# mini1284.net
KiCad netlist of a schematic drawn in EAGLE
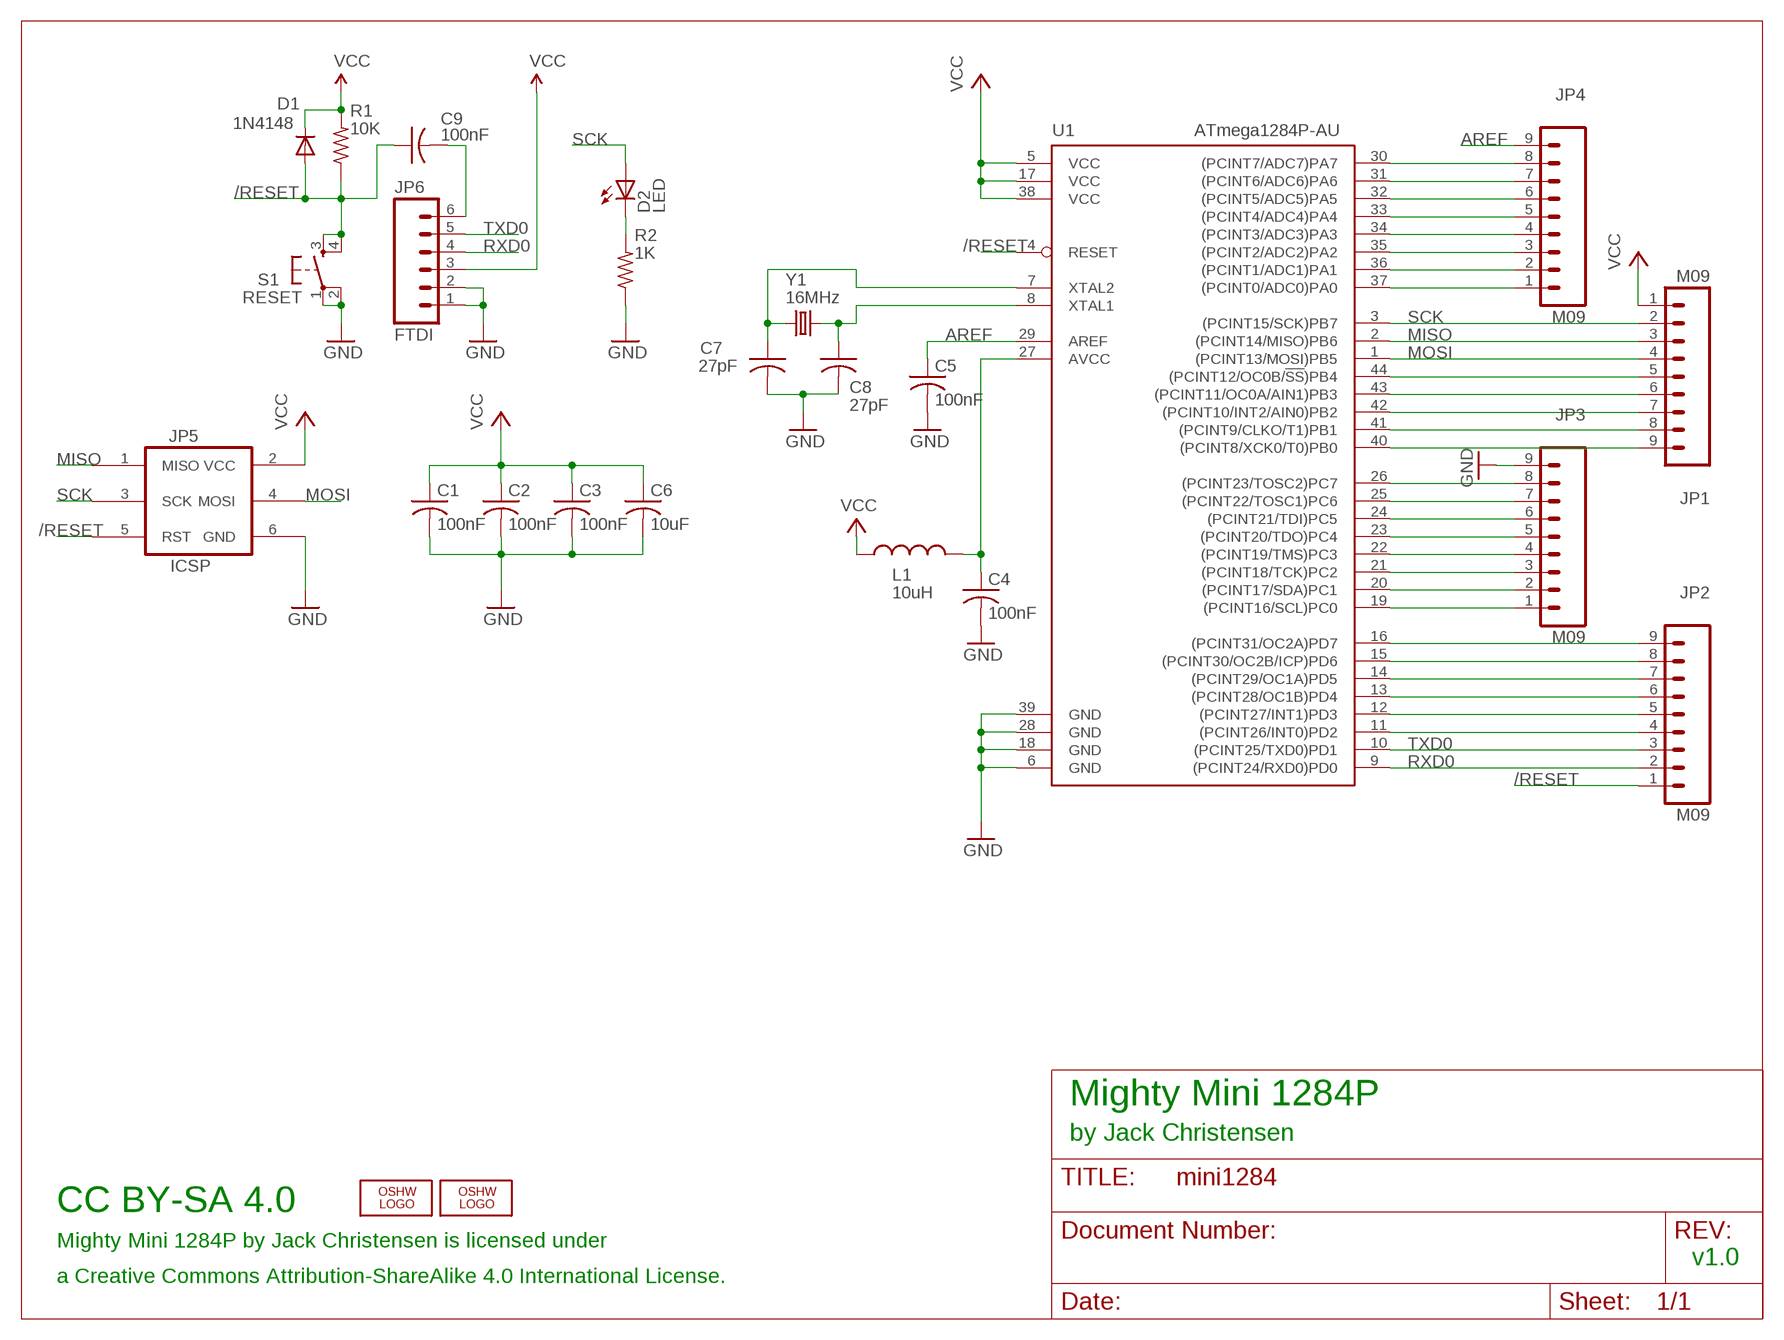
[diagram p0: schematic, sheet 1]

(export (version "E")
  (design (tool "Eeschema 10.0.6"))
  (components
    (comp (ref "C1")
      (value "100nF")
      (footprint "eagle-import:M0805")
      (libsource (lib "eagle-import") (part "C-USM0805"))
    )
    (comp (ref "C2")
      (value "100nF")
      (footprint "eagle-import:M0805")
      (libsource (lib "eagle-import") (part "C-USM0805"))
    )
    (comp (ref "C3")
      (value "100nF")
      (footprint "eagle-import:M0805")
      (libsource (lib "eagle-import") (part "C-USM0805"))
    )
    (comp (ref "C4")
      (value "100nF")
      (footprint "eagle-import:M0805")
      (libsource (lib "eagle-import") (part "C-USM0805"))
    )
    (comp (ref "C5")
      (value "100nF")
      (footprint "eagle-import:M0805")
      (libsource (lib "eagle-import") (part "C-USM0805"))
    )
    (comp (ref "C6")
      (value "10uF")
      (footprint "eagle-import:M1206")
      (libsource (lib "eagle-import") (part "C-USM1206"))
    )
    (comp (ref "C7")
      (value "27pF")
      (footprint "eagle-import:M0805")
      (libsource (lib "eagle-import") (part "C-USM0805"))
    )
    (comp (ref "C8")
      (value "27pF")
      (footprint "eagle-import:M0805")
      (libsource (lib "eagle-import") (part "C-USM0805"))
    )
    (comp (ref "C9")
      (value "100nF")
      (footprint "eagle-import:M0805")
      (libsource (lib "eagle-import") (part "C-USM0805"))
    )
    (comp (ref "D1")
      (value "1N4148")
      (footprint "eagle-import:SOD-323F-A")
      (libsource (lib "eagle-import") (part "DIODESOD-323F-A"))
    )
    (comp (ref "D2")
      (value "LED")
      (footprint "eagle-import:D0805A")
      (libsource (lib "eagle-import") (part "LEDD0805A"))
    )
    (comp (ref "JP1")
      (value "M09")
      (footprint "eagle-import:1X09")
      (libsource (lib "eagle-import") (part "M09"))
    )
    (comp (ref "JP2")
      (value "M09")
      (footprint "eagle-import:1X09")
      (libsource (lib "eagle-import") (part "M09"))
    )
    (comp (ref "JP3")
      (value "M09")
      (footprint "eagle-import:1X09")
      (libsource (lib "eagle-import") (part "M09"))
    )
    (comp (ref "JP4")
      (value "M09")
      (footprint "eagle-import:1X09")
      (libsource (lib "eagle-import") (part "M09"))
    )
    (comp (ref "JP5")
      (value "ICSP")
      (footprint "eagle-import:2X3_LOCK")
      (libsource (lib "eagle-import") (part "AVR_SPI_PRG_62X3_LOCK"))
    )
    (comp (ref "JP6")
      (value "FTDI")
      (footprint "eagle-import:1X06_LOCK")
      (libsource (lib "eagle-import") (part "M06LOCK"))
    )
    (comp (ref "L1")
      (value "10uH")
      (footprint "eagle-import:M0805")
      (libsource (lib "eagle-import") (part "INDUCTORM0805"))
    )
    (comp (ref "LOGO1")
      (value "OSHW_LOGO_8MILX0150-NT")
      (footprint "eagle-import:OSHW_8X150_NOTEXT")
      (libsource (lib "eagle-import") (part "OSHW_LOGO_8MILX0150-NT"))
    )
    (comp (ref "LOGO2")
      (value "OSHW_LOGO_6MILX0100-NT")
      (footprint "eagle-import:OSHW_6X100_NOTEXT")
      (libsource (lib "eagle-import") (part "OSHW_LOGO_6MILX0100-NT"))
    )
    (comp (ref "R1")
      (value "10K")
      (footprint "eagle-import:M0805")
      (libsource (lib "eagle-import") (part "R-US_M0805"))
    )
    (comp (ref "R2")
      (value "1K")
      (footprint "eagle-import:M0805")
      (libsource (lib "eagle-import") (part "R-US_M0805"))
    )
    (comp (ref "S1")
      (value "RESET")
      (footprint "eagle-import:PTS810")
      (libsource (lib "eagle-import") (part "10-XXPTS810"))
    )
    (comp (ref "U1")
      (value "ATmega1284P-AU")
      (footprint "eagle-import:TQFP44")
      (fields (field (name "MPN") "ATMEGA644PV-10AU"))
      (libsource (lib "eagle-import") (part "ATMEGA644A"))
    )
    (comp (ref "Y1")
      (value "16MHz")
      (footprint "eagle-import:CRYSTAL-ABRACON-ABM2")
      (libsource (lib "eagle-import") (part "CRYSTALABM2"))
    )
  )
  (nets
    (net (code "1") (name "/AREF") (class "Default")
      (node (ref "C5") (pin "1") (pinfunction "1_1") (pintype "passive"))
      (node (ref "JP4") (pin "9") (pinfunction "9_9") (pintype "passive"))
      (node (ref "U1") (pin "29") (pinfunction "AREF_29") (pintype "passive"))
    )
    (net (code "2") (name "/MISO") (class "Default")
      (node (ref "JP1") (pin "3") (pinfunction "3_3") (pintype "passive"))
      (node (ref "JP5") (pin "1") (pinfunction "MISO_1") (pintype "passive"))
      (node (ref "U1") (pin "2") (pinfunction "(PCINT14/MISO)PB6_2") (pintype "bidirectional"))
    )
    (net (code "3") (name "/MOSI") (class "Default")
      (node (ref "JP1") (pin "4") (pinfunction "4_4") (pintype "passive"))
      (node (ref "JP5") (pin "4") (pinfunction "MOSI_4") (pintype "passive"))
      (node (ref "U1") (pin "1") (pinfunction "(PCINT13/MOSI)PB5_1") (pintype "bidirectional"))
    )
    (net (code "4") (name "/RXD0") (class "Default")
      (node (ref "JP2") (pin "2") (pinfunction "2_2") (pintype "passive"))
      (node (ref "JP6") (pin "4") (pinfunction "4_4") (pintype "passive"))
      (node (ref "U1") (pin "9") (pinfunction "(PCINT24/RXD0)PD0_9") (pintype "bidirectional"))
    )
    (net (code "5") (name "/SCK") (class "Default")
      (node (ref "D2") (pin "A") (pinfunction "A_A") (pintype "passive"))
      (node (ref "JP1") (pin "2") (pinfunction "2_2") (pintype "passive"))
      (node (ref "JP5") (pin "3") (pinfunction "SCK_3") (pintype "passive"))
      (node (ref "U1") (pin "3") (pinfunction "(PCINT15/SCK)PB7_3") (pintype "bidirectional"))
    )
    (net (code "6") (name "/TXD0") (class "Default")
      (node (ref "JP2") (pin "3") (pinfunction "3_3") (pintype "passive"))
      (node (ref "JP6") (pin "5") (pinfunction "5_5") (pintype "passive"))
      (node (ref "U1") (pin "10") (pinfunction "(PCINT25/TXD0)PD1_10") (pintype "bidirectional"))
    )
    (net (code "7") (name "/{slash}RESET") (class "Default")
      (node (ref "C9") (pin "1") (pinfunction "1_1") (pintype "passive"))
      (node (ref "D1") (pin "A") (pinfunction "A_A") (pintype "passive"))
      (node (ref "JP2") (pin "1") (pinfunction "1_1") (pintype "passive"))
      (node (ref "JP5") (pin "5") (pinfunction "RST_5") (pintype "passive"))
      (node (ref "R1") (pin "1") (pinfunction "1_1") (pintype "passive"))
      (node (ref "S1") (pin "3") (pinfunction "S_3") (pintype "passive"))
      (node (ref "S1") (pin "4") (pinfunction "S1_4") (pintype "passive"))
      (node (ref "U1") (pin "4") (pinfunction "RESET_4") (pintype "input"))
    )
    (net (code "8") (name "GND") (class "Default")
      (node (ref "C1") (pin "2") (pinfunction "2_2") (pintype "passive"))
      (node (ref "C2") (pin "2") (pinfunction "2_2") (pintype "passive"))
      (node (ref "C3") (pin "2") (pinfunction "2_2") (pintype "passive"))
      (node (ref "C4") (pin "2") (pinfunction "2_2") (pintype "passive"))
      (node (ref "C5") (pin "2") (pinfunction "2_2") (pintype "passive"))
      (node (ref "C6") (pin "2") (pinfunction "2_2") (pintype "passive"))
      (node (ref "C7") (pin "2") (pinfunction "2_2") (pintype "passive"))
      (node (ref "C8") (pin "2") (pinfunction "2_2") (pintype "passive"))
      (node (ref "JP3") (pin "9") (pinfunction "9_9") (pintype "passive"))
      (node (ref "JP5") (pin "6") (pinfunction "GND_6") (pintype "passive"))
      (node (ref "JP6") (pin "1") (pinfunction "1_1") (pintype "passive"))
      (node (ref "JP6") (pin "2") (pinfunction "2_2") (pintype "passive"))
      (node (ref "R2") (pin "1") (pinfunction "1_1") (pintype "passive"))
      (node (ref "S1") (pin "1") (pinfunction "P_1") (pintype "passive"))
      (node (ref "S1") (pin "2") (pinfunction "P1_2") (pintype "passive"))
      (node (ref "U1") (pin "18") (pinfunction "GND_18") (pintype "power_in"))
      (node (ref "U1") (pin "28") (pinfunction "GND_28") (pintype "power_in"))
      (node (ref "U1") (pin "39") (pinfunction "GND_39") (pintype "power_in"))
      (node (ref "U1") (pin "6") (pinfunction "GND_6") (pintype "power_in"))
    )
    (net (code "9") (name "Net-(C9-Pad2)") (class "Default")
      (node (ref "C9") (pin "2") (pinfunction "2_2") (pintype "passive"))
      (node (ref "JP6") (pin "6") (pinfunction "6_6") (pintype "passive"))
    )
    (net (code "10") (name "Net-(D2-C)") (class "Default")
      (node (ref "D2") (pin "K") (pinfunction "C_K") (pintype "passive"))
      (node (ref "R2") (pin "2") (pinfunction "2_2") (pintype "passive"))
    )
    (net (code "11") (name "Net-(U1-(PCINT0{slash}ADC0)PA0)") (class "Default")
      (node (ref "JP4") (pin "1") (pinfunction "1_1") (pintype "passive"))
      (node (ref "U1") (pin "37") (pinfunction "(PCINT0/ADC0)PA0_37") (pintype "bidirectional"))
    )
    (net (code "12") (name "Net-(U1-(PCINT1{slash}ADC1)PA1)") (class "Default")
      (node (ref "JP4") (pin "2") (pinfunction "2_2") (pintype "passive"))
      (node (ref "U1") (pin "36") (pinfunction "(PCINT1/ADC1)PA1_36") (pintype "bidirectional"))
    )
    (net (code "13") (name "Net-(U1-(PCINT2{slash}ADC2)PA2)") (class "Default")
      (node (ref "JP4") (pin "3") (pinfunction "3_3") (pintype "passive"))
      (node (ref "U1") (pin "35") (pinfunction "(PCINT2/ADC2)PA2_35") (pintype "bidirectional"))
    )
    (net (code "14") (name "Net-(U1-(PCINT3{slash}ADC3)PA3)") (class "Default")
      (node (ref "JP4") (pin "4") (pinfunction "4_4") (pintype "passive"))
      (node (ref "U1") (pin "34") (pinfunction "(PCINT3/ADC3)PA3_34") (pintype "bidirectional"))
    )
    (net (code "15") (name "Net-(U1-(PCINT4{slash}ADC4)PA4)") (class "Default")
      (node (ref "JP4") (pin "5") (pinfunction "5_5") (pintype "passive"))
      (node (ref "U1") (pin "33") (pinfunction "(PCINT4/ADC4)PA4_33") (pintype "bidirectional"))
    )
    (net (code "16") (name "Net-(U1-(PCINT5{slash}ADC5)PA5)") (class "Default")
      (node (ref "JP4") (pin "6") (pinfunction "6_6") (pintype "passive"))
      (node (ref "U1") (pin "32") (pinfunction "(PCINT5/ADC5)PA5_32") (pintype "bidirectional"))
    )
    (net (code "17") (name "Net-(U1-(PCINT6{slash}ADC6)PA6)") (class "Default")
      (node (ref "JP4") (pin "7") (pinfunction "7_7") (pintype "passive"))
      (node (ref "U1") (pin "31") (pinfunction "(PCINT6/ADC6)PA6_31") (pintype "bidirectional"))
    )
    (net (code "18") (name "Net-(U1-(PCINT7{slash}ADC7)PA7)") (class "Default")
      (node (ref "JP4") (pin "8") (pinfunction "8_8") (pintype "passive"))
      (node (ref "U1") (pin "30") (pinfunction "(PCINT7/ADC7)PA7_30") (pintype "bidirectional"))
    )
    (net (code "19") (name "Net-(U1-(PCINT8{slash}XCK0{slash}T0)PB0)") (class "Default")
      (node (ref "JP1") (pin "9") (pinfunction "9_9") (pintype "passive"))
      (node (ref "U1") (pin "40") (pinfunction "(PCINT8/XCK0/T0)PB0_40") (pintype "bidirectional"))
    )
    (net (code "20") (name "Net-(U1-(PCINT9{slash}CLKO{slash}T1)PB1)") (class "Default")
      (node (ref "JP1") (pin "8") (pinfunction "8_8") (pintype "passive"))
      (node (ref "U1") (pin "41") (pinfunction "(PCINT9/CLKO/T1)PB1_41") (pintype "bidirectional"))
    )
    (net (code "21") (name "Net-(U1-(PCINT10{slash}INT2{slash}AIN0)PB2)") (class "Default")
      (node (ref "JP1") (pin "7") (pinfunction "7_7") (pintype "passive"))
      (node (ref "U1") (pin "42") (pinfunction "(PCINT10/INT2/AIN0)PB2_42") (pintype "bidirectional"))
    )
    (net (code "22") (name "Net-(U1-(PCINT11{slash}OC0A{slash}AIN1)PB3)") (class "Default")
      (node (ref "JP1") (pin "6") (pinfunction "6_6") (pintype "passive"))
      (node (ref "U1") (pin "43") (pinfunction "(PCINT11/OC0A/AIN1)PB3_43") (pintype "bidirectional"))
    )
    (net (code "23") (name "Net-(U1-(PCINT12{slash}OC0B{slash}~{SS})PB4)") (class "Default")
      (node (ref "JP1") (pin "5") (pinfunction "5_5") (pintype "passive"))
      (node (ref "U1") (pin "44") (pinfunction "(PCINT12/OC0B/~{SS})PB4_44") (pintype "bidirectional"))
    )
    (net (code "24") (name "Net-(U1-(PCINT16{slash}SCL)PC0)") (class "Default")
      (node (ref "JP3") (pin "1") (pinfunction "1_1") (pintype "passive"))
      (node (ref "U1") (pin "19") (pinfunction "(PCINT16/SCL)PC0_19") (pintype "output"))
    )
    (net (code "25") (name "Net-(U1-(PCINT17{slash}SDA)PC1)") (class "Default")
      (node (ref "JP3") (pin "2") (pinfunction "2_2") (pintype "passive"))
      (node (ref "U1") (pin "20") (pinfunction "(PCINT17/SDA)PC1_20") (pintype "output"))
    )
    (net (code "26") (name "Net-(U1-(PCINT18{slash}TCK)PC2)") (class "Default")
      (node (ref "JP3") (pin "3") (pinfunction "3_3") (pintype "passive"))
      (node (ref "U1") (pin "21") (pinfunction "(PCINT18/TCK)PC2_21") (pintype "output"))
    )
    (net (code "27") (name "Net-(U1-(PCINT19{slash}TMS)PC3)") (class "Default")
      (node (ref "JP3") (pin "4") (pinfunction "4_4") (pintype "passive"))
      (node (ref "U1") (pin "22") (pinfunction "(PCINT19/TMS)PC3_22") (pintype "output"))
    )
    (net (code "28") (name "Net-(U1-(PCINT20{slash}TDO)PC4)") (class "Default")
      (node (ref "JP3") (pin "5") (pinfunction "5_5") (pintype "passive"))
      (node (ref "U1") (pin "23") (pinfunction "(PCINT20/TDO)PC4_23") (pintype "output"))
    )
    (net (code "29") (name "Net-(U1-(PCINT21{slash}TDI)PC5)") (class "Default")
      (node (ref "JP3") (pin "6") (pinfunction "6_6") (pintype "passive"))
      (node (ref "U1") (pin "24") (pinfunction "(PCINT21/TDI)PC5_24") (pintype "output"))
    )
    (net (code "30") (name "Net-(U1-(PCINT22{slash}TOSC1)PC6)") (class "Default")
      (node (ref "JP3") (pin "7") (pinfunction "7_7") (pintype "passive"))
      (node (ref "U1") (pin "25") (pinfunction "(PCINT22/TOSC1)PC6_25") (pintype "output"))
    )
    (net (code "31") (name "Net-(U1-(PCINT23{slash}TOSC2)PC7)") (class "Default")
      (node (ref "JP3") (pin "8") (pinfunction "8_8") (pintype "passive"))
      (node (ref "U1") (pin "26") (pinfunction "(PCINT23/TOSC2)PC7_26") (pintype "output"))
    )
    (net (code "32") (name "Net-(U1-(PCINT26{slash}INT0)PD2)") (class "Default")
      (node (ref "JP2") (pin "4") (pinfunction "4_4") (pintype "passive"))
      (node (ref "U1") (pin "11") (pinfunction "(PCINT26/INT0)PD2_11") (pintype "bidirectional"))
    )
    (net (code "33") (name "Net-(U1-(PCINT27{slash}INT1)PD3)") (class "Default")
      (node (ref "JP2") (pin "5") (pinfunction "5_5") (pintype "passive"))
      (node (ref "U1") (pin "12") (pinfunction "(PCINT27/INT1)PD3_12") (pintype "bidirectional"))
    )
    (net (code "34") (name "Net-(U1-(PCINT28{slash}OC1B)PD4)") (class "Default")
      (node (ref "JP2") (pin "6") (pinfunction "6_6") (pintype "passive"))
      (node (ref "U1") (pin "13") (pinfunction "(PCINT28/OC1B)PD4_13") (pintype "bidirectional"))
    )
    (net (code "35") (name "Net-(U1-(PCINT29{slash}OC1A)PD5)") (class "Default")
      (node (ref "JP2") (pin "7") (pinfunction "7_7") (pintype "passive"))
      (node (ref "U1") (pin "14") (pinfunction "(PCINT29/OC1A)PD5_14") (pintype "bidirectional"))
    )
    (net (code "36") (name "Net-(U1-(PCINT30{slash}OC2B{slash}ICP)PD6)") (class "Default")
      (node (ref "JP2") (pin "8") (pinfunction "8_8") (pintype "passive"))
      (node (ref "U1") (pin "15") (pinfunction "(PCINT30/OC2B/ICP)PD6_15") (pintype "bidirectional"))
    )
    (net (code "37") (name "Net-(U1-(PCINT31{slash}OC2A)PD7)") (class "Default")
      (node (ref "JP2") (pin "9") (pinfunction "9_9") (pintype "passive"))
      (node (ref "U1") (pin "16") (pinfunction "(PCINT31/OC2A)PD7_16") (pintype "bidirectional"))
    )
    (net (code "38") (name "Net-(U1-AVCC)") (class "Default")
      (node (ref "C4") (pin "1") (pinfunction "1_1") (pintype "passive"))
      (node (ref "L1") (pin "2") (pinfunction "2_2") (pintype "passive"))
      (node (ref "U1") (pin "27") (pinfunction "AVCC_27") (pintype "power_in"))
    )
    (net (code "39") (name "Net-(U1-XTAL1)") (class "Default")
      (node (ref "C8") (pin "1") (pinfunction "1_1") (pintype "passive"))
      (node (ref "U1") (pin "8") (pinfunction "XTAL1_8") (pintype "bidirectional"))
      (node (ref "Y1") (pin "P$2") (pinfunction "2_P$2") (pintype "passive"))
    )
    (net (code "40") (name "Net-(U1-XTAL2)") (class "Default")
      (node (ref "C7") (pin "1") (pinfunction "1_1") (pintype "passive"))
      (node (ref "U1") (pin "7") (pinfunction "XTAL2_7") (pintype "bidirectional"))
      (node (ref "Y1") (pin "P$1") (pinfunction "1_P$1") (pintype "passive"))
    )
    (net (code "41") (name "VCC") (class "Default")
      (node (ref "C1") (pin "1") (pinfunction "1_1") (pintype "passive"))
      (node (ref "C2") (pin "1") (pinfunction "1_1") (pintype "passive"))
      (node (ref "C3") (pin "1") (pinfunction "1_1") (pintype "passive"))
      (node (ref "C6") (pin "1") (pinfunction "1_1") (pintype "passive"))
      (node (ref "D1") (pin "K") (pinfunction "K_K") (pintype "passive"))
      (node (ref "JP1") (pin "1") (pinfunction "1_1") (pintype "passive"))
      (node (ref "JP5") (pin "2") (pinfunction "VCC_2") (pintype "passive"))
      (node (ref "JP6") (pin "3") (pinfunction "3_3") (pintype "passive"))
      (node (ref "L1") (pin "1") (pinfunction "1_1") (pintype "passive"))
      (node (ref "R1") (pin "2") (pinfunction "2_2") (pintype "passive"))
      (node (ref "U1") (pin "17") (pinfunction "VCC_17") (pintype "power_in"))
      (node (ref "U1") (pin "38") (pinfunction "VCC_38") (pintype "power_in"))
      (node (ref "U1") (pin "5") (pinfunction "VCC_5") (pintype "power_in"))
    )
  )
)
